# JL7016G8.net
KiCad netlist of a schematic drawn in Altium Designer
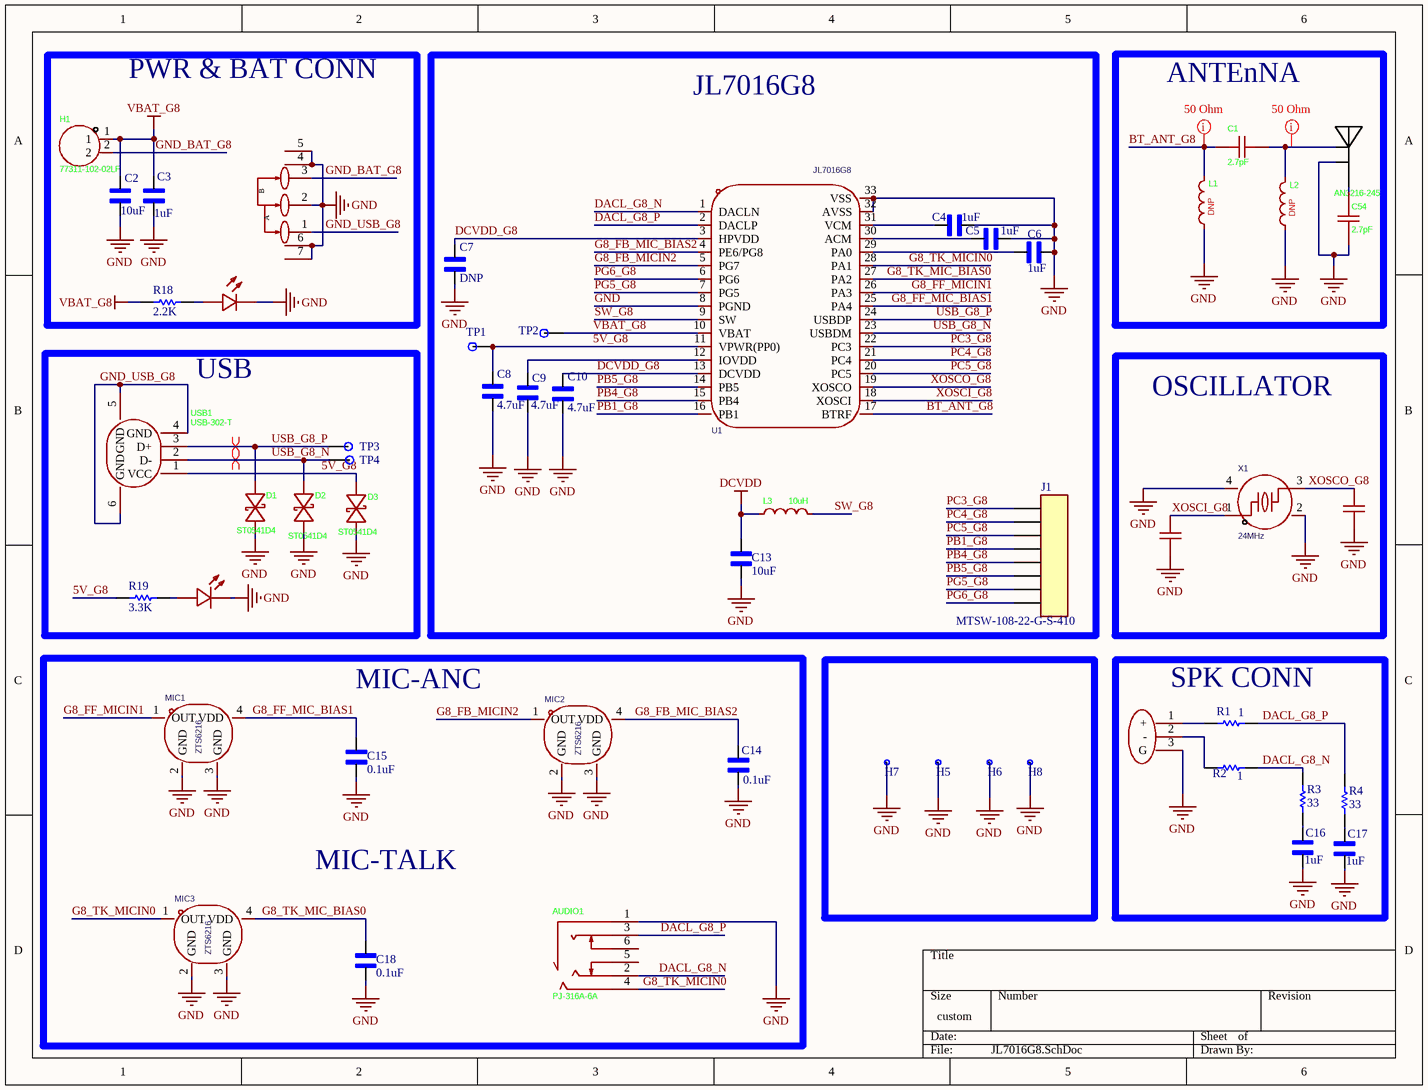
[diagram p0: JL7016G8.SchDoc]

(export (version "E")
  (design (tool "Eeschema 10.0.6"))
  (components
    (comp (ref "ANT1")
      (value "AN3216-245")
      (footprint "CUSTOME ANTEENA")
      (fields (field (name "MANUFACTURER") "Rainsun(霖昱微)") (field (name "POWER") "1W"))
      (libsource (lib "JEILI_DEV_BOARD") (part "AN3216-245"))
    )
    (comp (ref "AUDIO1")
      (value "PJ-316A-6A")
      (footprint "AUDIO-SMD_PJ-316A-6A")
      (fields (field (name "MANUFACTURER") "韩国韩荣"))
      (libsource (lib "JEILI_DEV_BOARD") (part "PJ-316A-6A"))
    )
    (comp (ref "C1")
      (value "2.7pF")
      (footprint "C0603")
      (fields (field (name "MANUFACTURER") "FH(风华)") (field (name "MANUFACTURER PART") "0603CG2R7C500NT"))
      (libsource (lib "JEILI_DEV_BOARD") (part "0603CG2R7C500NT"))
    )
    (comp (ref "C2")
      (value "10uF")
      (footprint "CAPC3216X170N")
      (libsource (lib "JEILI_DEV_BOARD") (part "CAP_10F"))
    )
    (comp (ref "C3")
      (value "1uF")
      (footprint "CAPC3216X170N")
      (libsource (lib "JEILI_DEV_BOARD") (part "CAP_1uF"))
    )
    (comp (ref "C4") (value "1uF") (footprint "CAPC3216X170N") (libsource (lib "") (part "CAP_1uF_2")))
    (comp (ref "C5") (value "1uF") (footprint "CAPC3216X170N") (libsource (lib "") (part "CAP_1uF_2")))
    (comp (ref "C6") (value "1uF") (footprint "CAPC3216X170N") (libsource (lib "") (part "CAP_1uF_2")))
    (comp (ref "C7")
      (value "DNP")
      (footprint "CAPC3216X170N")
      (fields (field (name "Comment") "1uF"))
      (libsource (lib "JEILI_DEV_BOARD") (part "CAP_1uF"))
    )
    (comp (ref "C8")
      (value "4.7uF")
      (footprint "CAPC3216X170N")
      (fields (field (name "Comment") "1uF"))
      (libsource (lib "JEILI_DEV_BOARD") (part "CAP_1uF"))
    )
    (comp (ref "C9")
      (value "4.7uF")
      (footprint "CAPC3216X170N")
      (fields (field (name "Comment") "1uF"))
      (libsource (lib "JEILI_DEV_BOARD") (part "CAP_1uF"))
    )
    (comp (ref "C10")
      (value "4.7uF")
      (footprint "CAPC3216X170N")
      (fields (field (name "Comment") "1uF"))
      (libsource (lib "JEILI_DEV_BOARD") (part "CAP_1uF"))
    )
    (comp (ref "C11")
      (value "12pF")
      (footprint "CAPC3216X170N")
      (fields
        (field (name "MANUFACTURER") "FH(风华)")
        (field (name "MANUFACTURER PART") "0402CG120J500NT")
        (field (name "TOLERANCE") "±5%")
      )
      (libsource (lib "JEILI_DEV_BOARD") (part "0402CG120J500NT"))
    )
    (comp (ref "C12")
      (value "12pF")
      (footprint "CAPC3216X170N")
      (fields
        (field (name "MANUFACTURER") "FH(风华)")
        (field (name "MANUFACTURER PART") "0402CG120J500NT")
        (field (name "TOLERANCE") "±5%")
      )
      (libsource (lib "JEILI_DEV_BOARD") (part "0402CG120J500NT"))
    )
    (comp (ref "C13")
      (value "10uF")
      (footprint "CAPC3216X170N")
      (libsource (lib "JEILI_DEV_BOARD") (part "CAP_10F"))
    )
    (comp (ref "C14")
      (value "0.1uF")
      (footprint "CAPC3216X170N")
      (description "100nF 10V X7R ±5% 0402 Multilayer Ceramic Capacitors MLCC - SMD/SMT ROHS")
      (fields (field (name "MANUFACTURER") "Walsin Tech Corp") (field (name "MFR.PART #") "0402B104J100CT"))
      (libsource (lib "Glasses_EEG_V2.0") (part "CAP_0.1uF"))
    )
    (comp (ref "C15")
      (value "0.1uF")
      (footprint "CAPC3216X170N")
      (description "100nF 10V X7R ±5% 0402 Multilayer Ceramic Capacitors MLCC - SMD/SMT ROHS")
      (fields (field (name "MANUFACTURER") "Walsin Tech Corp") (field (name "MFR.PART #") "0402B104J100CT"))
      (libsource (lib "Glasses_EEG_V2.0") (part "CAP_0.1uF"))
    )
    (comp (ref "C16") (value "1uF") (footprint "CAPC3216X170N") (libsource (lib "") (part "CAP_1uF_1")))
    (comp (ref "C17") (value "1uF") (footprint "CAPC3216X170N") (libsource (lib "") (part "CAP_1uF_1")))
    (comp (ref "C18")
      (value "0.1uF")
      (footprint "CAPC3216X170N")
      (description "100nF 10V X7R ±5% 0402 Multilayer Ceramic Capacitors MLCC - SMD/SMT ROHS")
      (fields (field (name "MANUFACTURER") "Walsin Tech Corp") (field (name "MFR.PART #") "0402B104J100CT"))
      (libsource (lib "Glasses_EEG_V2.0") (part "CAP_0.1uF"))
    )
    (comp (ref "C54")
      (value "2.7pF")
      (footprint "C0402")
      (fields (field (name "MANUFACTURER") "FH(风华)") (field (name "MANUFACTURER PART") "0603CG2R7C500NT"))
      (libsource (lib "JEILI_DEV_BOARD") (part "0603CG2R7C500NT"))
    )
    (comp (ref "D1")
      (value "ST0541D4")
      (footprint "DFN1006-BI")
      (fields (field (name "MANUFACTURER") "Leiditech(雷卯电子)"))
      (libsource (lib "JEILI_DEV_BOARD") (part "ST0541D4"))
    )
    (comp (ref "D2")
      (value "ST0541D4")
      (footprint "DFN1006-BI")
      (fields (field (name "MANUFACTURER") "Leiditech(雷卯电子)"))
      (libsource (lib "JEILI_DEV_BOARD") (part "ST0541D4"))
    )
    (comp (ref "D3")
      (value "ST0541D4")
      (footprint "DFN1006-BI")
      (fields (field (name "MANUFACTURER") "Leiditech(雷卯电子)"))
      (libsource (lib "JEILI_DEV_BOARD") (part "ST0541D4"))
    )
    (comp (ref "H1")
      (value "77311-102-02LF")
      (footprint "HDR-TH_2P-P2.54-V-M-1")
      (fields (field (name "MANUFACTURER") "Amphenol"))
      (libsource (lib "JEILI_DEV_BOARD") (part "77311-102-02LF"))
    )
    (comp (ref "H5") (value "MH") (footprint "MH") (libsource (lib "JEILI_DEV_BOARD") (part "MH")))
    (comp (ref "H6") (value "MH") (footprint "MH") (libsource (lib "JEILI_DEV_BOARD") (part "MH")))
    (comp (ref "H7") (value "MH") (footprint "MH") (libsource (lib "JEILI_DEV_BOARD") (part "MH")))
    (comp (ref "H8") (value "MH") (footprint "MH") (libsource (lib "JEILI_DEV_BOARD") (part "MH")))
    (comp (ref "J1")
      (value "MTSW-108-22-G-S-410")
      (footprint "SAMTEC_MTSW-108-22-G-S-410")
      (libsource (lib "JEILI_DEV_BOARD") (part "MTSW-108-22-G-S-410"))
    )
    (comp (ref "L1")
      (value "DNP")
      (footprint "L0603")
      (fields
        (field (name "MANUFACTURER") "muRata(村田)")
        (field (name "MANUFACTURER PART") "DFE18SAN1R0ME0L")
        (field (name "TOLERANCE") "±20%")
      )
      (libsource (lib "JEILI_DEV_BOARD") (part "33nH"))
    )
    (comp (ref "L2")
      (value "DNP")
      (footprint "L0603")
      (fields
        (field (name "MANUFACTURER") "muRata(村田)")
        (field (name "MANUFACTURER PART") "DFE18SAN1R0ME0L")
        (field (name "TOLERANCE") "±20%")
      )
      (libsource (lib "JEILI_DEV_BOARD") (part "33nH"))
    )
    (comp (ref "L3") (value "10uH") (footprint "L0603") (libsource (lib "JEILI_DEV_BOARD") (part "10uH")))
    (comp (ref "LED1")
      (value "LTST-C191GKT")
      (footprint "LED0603-R-RD_GREEN")
      (fields (field (name "MANUFACTURER") "LITEON(光宝)"))
      (libsource (lib "JEILI_DEV_BOARD") (part "LTST-C191GKT"))
    )
    (comp (ref "LED2")
      (value "KT-0603R")
      (footprint "LED0603-RD")
      (fields (field (name "MANUFACTURER") "KENTO"))
      (libsource (lib "JEILI_DEV_BOARD") (part "KT-0603R"))
    )
    (comp (ref "MIC1")
      (value "ZTS6216")
      (footprint "MIC-SMD_4P-L2.8-W1.9-P1.84-TL")
      (fields (field (name "MANUFACTURER") "ZILLTEK(钰太)"))
      (libsource (lib "Glasses_EEG_V2.0") (part "ZTS6216"))
    )
    (comp (ref "MIC2")
      (value "ZTS6216")
      (footprint "MIC-SMD_4P-L2.8-W1.9-P1.84-TL")
      (fields (field (name "MANUFACTURER") "ZILLTEK(钰太)"))
      (libsource (lib "Glasses_EEG_V2.0") (part "ZTS6216"))
    )
    (comp (ref "MIC3")
      (value "ZTS6216")
      (footprint "MIC-SMD_4P-L2.8-W1.9-P1.84-TL")
      (fields (field (name "MANUFACTURER") "ZILLTEK(钰太)"))
      (libsource (lib "Glasses_EEG_V2.0") (part "ZTS6216"))
    )
    (comp (ref "P1")
      (value "1.27-1*3P针")
      (footprint "HDR-TH_3P-P1.27-V-M-1")
      (fields (field (name "MANUFACTURER") "BOOMELE(博穆精密)"))
      (libsource (lib "JEILI_DEV_BOARD") (part "1.27-1*3P针"))
    )
    (comp (ref "R1")
      (value "1")
      (footprint "R0603")
      (fields
        (field (name "MANUFACTURER") "YAGEO")
        (field (name "MFR.PART #") "RC0402JR-0733RL")
        (field (name "JLCPCB PART #") "C137880")
      )
      (libsource (lib "JEILI_DEV_BOARD") (part "RES_1"))
    )
    (comp (ref "R2")
      (value "1")
      (footprint "R0603")
      (fields
        (field (name "MANUFACTURER") "YAGEO")
        (field (name "MFR.PART #") "RC0402JR-0733RL")
        (field (name "JLCPCB PART #") "C137880")
      )
      (libsource (lib "JEILI_DEV_BOARD") (part "RES_1"))
    )
    (comp (ref "R3")
      (value "33")
      (footprint "R0603")
      (fields
        (field (name "MANUFACTURER") "YAGEO")
        (field (name "MFR.PART #") "RC0402JR-0733RL")
        (field (name "JLCPCB PART #") "C137880")
      )
      (libsource (lib "JEILI_DEV_BOARD") (part "RES_33"))
    )
    (comp (ref "R4")
      (value "33")
      (footprint "R0603")
      (fields
        (field (name "MANUFACTURER") "YAGEO")
        (field (name "MFR.PART #") "RC0402JR-0733RL")
        (field (name "JLCPCB PART #") "C137880")
      )
      (libsource (lib "JEILI_DEV_BOARD") (part "RES_33"))
    )
    (comp (ref "R18")
      (value "2.2K")
      (footprint "R1206")
      (fields
        (field (name "MANUFACTURER") "YAGEO")
        (field (name "MFR.PART #") "RC0402JR-0733RL")
        (field (name "JLCPCB PART #") "C137880")
      )
      (libsource (lib "JEILI_DEV_BOARD") (part "RES_2.2K"))
    )
    (comp (ref "R19")
      (value "3.3K")
      (footprint "R1206")
      (fields
        (field (name "MANUFACTURER") "YAGEO")
        (field (name "MFR.PART #") "RC0402JR-0733RL")
        (field (name "JLCPCB PART #") "C137880")
      )
      (libsource (lib "JEILI_DEV_BOARD") (part "RES_3.3K"))
    )
    (comp (ref "SW1")
      (value "MK-12C02-G015")
      (footprint "SW-SMD_G-SWITCH_MK-12C02-G015")
      (fields (field (name "MANUFACTURER") "G-Switch(品赞)"))
      (libsource (lib "JEILI_DEV_BOARD") (part "MK-12C02-G015_C2911519"))
    )
    (comp (ref "TP1")
      (value "TP_1")
      (footprint "TP")
      (description "test point")
      (libsource (lib "JEILI_DEV_BOARD") (part "TP_1"))
    )
    (comp (ref "TP2")
      (value "TP_1")
      (footprint "TP")
      (description "test point")
      (libsource (lib "JEILI_DEV_BOARD") (part "TP_1"))
    )
    (comp (ref "TP3")
      (value "TP_1")
      (footprint "TP")
      (description "test point")
      (libsource (lib "JEILI_DEV_BOARD") (part "TP_1"))
    )
    (comp (ref "TP4")
      (value "TP_1")
      (footprint "TP")
      (description "test point")
      (libsource (lib "JEILI_DEV_BOARD") (part "TP_1"))
    )
    (comp (ref "U1")
      (value "JL7016G8")
      (footprint "QFN-32_L4.0-W4.0-P0.40-TL-EP2.7")
      (fields (field (name "MANUFACTURER") "JL(杰理)"))
      (libsource (lib "JEILI_DEV_BOARD") (part "JL7016G8"))
    )
    (comp (ref "USB1")
      (value "USB-302-T")
      (footprint "USB-A-TH_USB-302-T")
      (fields (field (name "MANUFACTURER") "SOFNG(硕方)"))
      (libsource (lib "JEILI_DEV_BOARD") (part "USB-302-T"))
    )
    (comp (ref "X1")
      (value "24MHz")
      (footprint "CRYSTAL-SMD_4P-L2.0-W1.6-BL-A")
      (fields
        (field (name "MANUFACTURER") "YXC(扬兴晶振)")
        (field (name "MANUFACTURER PART") "XL7EL89CKI-111YLC-24M")
      )
      (libsource (lib "Glasses_EEG_V2.0") (part "XL7EL89CKI-111YLC-24M"))
    )
  )
  (nets
    (net (code "1") (name "/5V_G8") (class "Default")
      (node (ref "C8") (pin "1") (pinfunction "1_1") (pintype "passive"))
      (node (ref "D3") (pin "2") (pinfunction "2_2") (pintype "passive"))
      (node (ref "R19") (pin "2") (pinfunction "2_2") (pintype "passive"))
      (node (ref "TP1") (pin "1") (pinfunction "1_1") (pintype "passive"))
      (node (ref "U1") (pin "11") (pinfunction "VPWR(PP0)_11") (pintype "passive"))
      (node (ref "USB1") (pin "1") (pinfunction "VCC_1") (pintype "passive"))
    )
    (net (code "2") (name "/BT_ANT_G8") (class "Default")
      (node (ref "C1") (pin "1") (pinfunction "1_1") (pintype "passive"))
      (node (ref "L1") (pin "2") (pinfunction "2_2") (pintype "passive"))
      (node (ref "U1") (pin "17") (pinfunction "BTRF_17") (pintype "passive"))
    )
    (net (code "3") (name "/DACL_G8_N") (class "Default")
      (node (ref "AUDIO1") (pin "2") (pinfunction "2_2") (pintype "passive"))
      (node (ref "R2") (pin "1") (pinfunction "1_1") (pintype "passive"))
      (node (ref "R3") (pin "1") (pinfunction "1_1") (pintype "passive"))
      (node (ref "U1") (pin "1") (pinfunction "DACLN_1") (pintype "passive"))
    )
    (net (code "4") (name "/DACL_G8_P") (class "Default")
      (node (ref "AUDIO1") (pin "3") (pinfunction "3_3") (pintype "passive"))
      (node (ref "R1") (pin "1") (pinfunction "1_1") (pintype "passive"))
      (node (ref "R4") (pin "1") (pinfunction "1_1") (pintype "passive"))
      (node (ref "U1") (pin "2") (pinfunction "DACLP_2") (pintype "passive"))
    )
    (net (code "5") (name "/DCVDD_G8") (class "Default")
      (node (ref "C10") (pin "1") (pinfunction "1_1") (pintype "passive"))
      (node (ref "C7") (pin "1") (pinfunction "1_1") (pintype "passive"))
      (node (ref "U1") (pin "13") (pinfunction "DCVDD_13") (pintype "passive"))
      (node (ref "U1") (pin "3") (pinfunction "HPVDD_3") (pintype "passive"))
    )
    (net (code "6") (name "/G8_FB_MICIN2") (class "Default")
      (node (ref "MIC2") (pin "1") (pinfunction "OUT_1") (pintype "passive"))
      (node (ref "U1") (pin "5") (pinfunction "PG7_5") (pintype "passive"))
    )
    (net (code "7") (name "/G8_FB_MIC_BIAS2") (class "Default")
      (node (ref "C14") (pin "2") (pinfunction "2_2") (pintype "passive"))
      (node (ref "MIC2") (pin "4") (pinfunction "VDD_4") (pintype "passive"))
      (node (ref "U1") (pin "4") (pinfunction "PE6/PG8_4") (pintype "passive"))
    )
    (net (code "8") (name "/G8_FF_MICIN1") (class "Default")
      (node (ref "MIC1") (pin "1") (pinfunction "OUT_1") (pintype "passive"))
      (node (ref "U1") (pin "26") (pinfunction "PA3_26") (pintype "passive"))
    )
    (net (code "9") (name "/G8_FF_MIC_BIAS1") (class "Default")
      (node (ref "C15") (pin "2") (pinfunction "2_2") (pintype "passive"))
      (node (ref "MIC1") (pin "4") (pinfunction "VDD_4") (pintype "passive"))
      (node (ref "U1") (pin "25") (pinfunction "PA4_25") (pintype "passive"))
    )
    (net (code "10") (name "/G8_TK_MICIN0") (class "Default")
      (node (ref "AUDIO1") (pin "4") (pinfunction "4_4") (pintype "passive"))
      (node (ref "MIC3") (pin "1") (pinfunction "OUT_1") (pintype "passive"))
      (node (ref "U1") (pin "28") (pinfunction "PA1_28") (pintype "passive"))
    )
    (net (code "11") (name "/G8_TK_MIC_BIAS0") (class "Default")
      (node (ref "C18") (pin "2") (pinfunction "2_2") (pintype "passive"))
      (node (ref "MIC3") (pin "4") (pinfunction "VDD_4") (pintype "passive"))
      (node (ref "U1") (pin "27") (pinfunction "PA2_27") (pintype "passive"))
    )
    (net (code "12") (name "/GND_BAT_G8") (class "Default")
      (node (ref "H1") (pin "2") (pinfunction "2_2") (pintype "passive"))
      (node (ref "SW1") (pin "3") (pinfunction "3_3") (pintype "passive"))
    )
    (net (code "13") (name "/GND_USB_G8") (class "Default")
      (node (ref "SW1") (pin "1") (pinfunction "1_1") (pintype "passive"))
      (node (ref "USB1") (pin "4") (pinfunction "GND_4") (pintype "passive"))
      (node (ref "USB1") (pin "5") (pinfunction "GND_5") (pintype "passive"))
      (node (ref "USB1") (pin "6") (pinfunction "GND_6") (pintype "passive"))
    )
    (net (code "14") (name "/PB1_G8") (class "Default")
      (node (ref "J1") (pin "04") (pinfunction "04_04") (pintype "passive"))
      (node (ref "U1") (pin "16") (pinfunction "PB1_16") (pintype "passive"))
    )
    (net (code "15") (name "/PB4_G8") (class "Default")
      (node (ref "J1") (pin "05") (pinfunction "05_05") (pintype "passive"))
      (node (ref "U1") (pin "15") (pinfunction "PB4_15") (pintype "passive"))
    )
    (net (code "16") (name "/PB5_G8") (class "Default")
      (node (ref "J1") (pin "06") (pinfunction "06_06") (pintype "passive"))
      (node (ref "U1") (pin "14") (pinfunction "PB5_14") (pintype "passive"))
    )
    (net (code "17") (name "/PC3_G8") (class "Default")
      (node (ref "J1") (pin "01") (pinfunction "01_01") (pintype "passive"))
      (node (ref "U1") (pin "22") (pinfunction "PC3_22") (pintype "passive"))
    )
    (net (code "18") (name "/PC4_G8") (class "Default")
      (node (ref "J1") (pin "02") (pinfunction "02_02") (pintype "passive"))
      (node (ref "U1") (pin "21") (pinfunction "PC4_21") (pintype "passive"))
    )
    (net (code "19") (name "/PC5_G8") (class "Default")
      (node (ref "J1") (pin "03") (pinfunction "03_03") (pintype "passive"))
      (node (ref "U1") (pin "20") (pinfunction "PC5_20") (pintype "passive"))
    )
    (net (code "20") (name "/PG5_G8") (class "Default")
      (node (ref "J1") (pin "07") (pinfunction "07_07") (pintype "passive"))
      (node (ref "U1") (pin "7") (pinfunction "PG5_7") (pintype "passive"))
    )
    (net (code "21") (name "/PG6_G8") (class "Default")
      (node (ref "J1") (pin "08") (pinfunction "08_08") (pintype "passive"))
      (node (ref "U1") (pin "6") (pinfunction "PG6_6") (pintype "passive"))
    )
    (net (code "22") (name "/SW_G8") (class "Default")
      (node (ref "L3") (pin "2") (pinfunction "2_2") (pintype "passive"))
      (node (ref "U1") (pin "9") (pinfunction "SW_9") (pintype "passive"))
    )
    (net (code "23") (name "/USB_G8_N") (class "Default")
      (node (ref "D2") (pin "2") (pinfunction "2_2") (pintype "passive"))
      (node (ref "TP4") (pin "1") (pinfunction "1_1") (pintype "passive"))
      (node (ref "U1") (pin "23") (pinfunction "USBDM_23") (pintype "passive"))
      (node (ref "USB1") (pin "2") (pinfunction "D-_2") (pintype "passive"))
    )
    (net (code "24") (name "/USB_G8_P") (class "Default")
      (node (ref "D1") (pin "2") (pinfunction "2_2") (pintype "passive"))
      (node (ref "TP3") (pin "1") (pinfunction "1_1") (pintype "passive"))
      (node (ref "U1") (pin "24") (pinfunction "USBDP_24") (pintype "passive"))
      (node (ref "USB1") (pin "3") (pinfunction "D+_3") (pintype "passive"))
    )
    (net (code "25") (name "/XOSCI_G8") (class "Default")
      (node (ref "C12") (pin "2") (pinfunction "2_2") (pintype "passive"))
      (node (ref "U1") (pin "18") (pinfunction "XOSCI_18") (pintype "passive"))
      (node (ref "X1") (pin "1") (pinfunction "1_1") (pintype "passive"))
    )
    (net (code "26") (name "/XOSCO_G8") (class "Default")
      (node (ref "C11") (pin "2") (pinfunction "2_2") (pintype "passive"))
      (node (ref "U1") (pin "19") (pinfunction "XOSCO_19") (pintype "passive"))
      (node (ref "X1") (pin "3") (pinfunction "3_3") (pintype "passive"))
    )
    (net (code "27") (name "DCVDD") (class "Default")
      (node (ref "C13") (pin "2") (pinfunction "2_2") (pintype "passive"))
      (node (ref "L3") (pin "1") (pinfunction "1_1") (pintype "passive"))
    )
    (net (code "28") (name "GND") (class "Default")
      (node (ref "ANT1") (pin "2") (pinfunction "2_2") (pintype "passive"))
      (node (ref "AUDIO1") (pin "1") (pinfunction "1_1") (pintype "passive"))
      (node (ref "C10") (pin "2") (pinfunction "2_2") (pintype "passive"))
      (node (ref "C11") (pin "1") (pinfunction "1_1") (pintype "passive"))
      (node (ref "C12") (pin "1") (pinfunction "1_1") (pintype "passive"))
      (node (ref "C13") (pin "1") (pinfunction "1_1") (pintype "passive"))
      (node (ref "C14") (pin "1") (pinfunction "1_1") (pintype "passive"))
      (node (ref "C15") (pin "1") (pinfunction "1_1") (pintype "passive"))
      (node (ref "C16") (pin "1") (pinfunction "1_1") (pintype "passive"))
      (node (ref "C17") (pin "1") (pinfunction "1_1") (pintype "passive"))
      (node (ref "C18") (pin "1") (pinfunction "1_1") (pintype "passive"))
      (node (ref "C2") (pin "1") (pinfunction "1_1") (pintype "passive"))
      (node (ref "C3") (pin "2") (pinfunction "2_2") (pintype "passive"))
      (node (ref "C4") (pin "2") (pinfunction "2_2") (pintype "passive"))
      (node (ref "C5") (pin "2") (pinfunction "2_2") (pintype "passive"))
      (node (ref "C54") (pin "1") (pinfunction "1_1") (pintype "passive"))
      (node (ref "C6") (pin "2") (pinfunction "2_2") (pintype "passive"))
      (node (ref "C7") (pin "2") (pinfunction "2_2") (pintype "passive"))
      (node (ref "C8") (pin "2") (pinfunction "2_2") (pintype "passive"))
      (node (ref "C9") (pin "2") (pinfunction "2_2") (pintype "passive"))
      (node (ref "D1") (pin "1") (pinfunction "1_1") (pintype "passive"))
      (node (ref "D2") (pin "1") (pinfunction "1_1") (pintype "passive"))
      (node (ref "D3") (pin "1") (pinfunction "1_1") (pintype "passive"))
      (node (ref "H5") (pin "1") (pinfunction "1_1") (pintype "passive"))
      (node (ref "H6") (pin "1") (pinfunction "1_1") (pintype "passive"))
      (node (ref "H7") (pin "1") (pinfunction "1_1") (pintype "passive"))
      (node (ref "H8") (pin "1") (pinfunction "1_1") (pintype "passive"))
      (node (ref "L1") (pin "1") (pinfunction "1_1") (pintype "passive"))
      (node (ref "L2") (pin "1") (pinfunction "1_1") (pintype "passive"))
      (node (ref "LED1") (pin "2") (pinfunction "C_2") (pintype "passive"))
      (node (ref "LED2") (pin "1") (pinfunction "K_1") (pintype "passive"))
      (node (ref "MIC1") (pin "2") (pinfunction "GND_2") (pintype "passive"))
      (node (ref "MIC1") (pin "3") (pinfunction "GND_3") (pintype "passive"))
      (node (ref "MIC2") (pin "2") (pinfunction "GND_2") (pintype "passive"))
      (node (ref "MIC2") (pin "3") (pinfunction "GND_3") (pintype "passive"))
      (node (ref "MIC3") (pin "2") (pinfunction "GND_2") (pintype "passive"))
      (node (ref "MIC3") (pin "3") (pinfunction "GND_3") (pintype "passive"))
      (node (ref "P1") (pin "3") (pinfunction "G_3") (pintype "passive"))
      (node (ref "SW1") (pin "2") (pinfunction "2_2") (pintype "passive"))
      (node (ref "SW1") (pin "4") (pinfunction "4_4") (pintype "passive"))
      (node (ref "SW1") (pin "5") (pinfunction "5_5") (pintype "passive"))
      (node (ref "SW1") (pin "6") (pinfunction "6_6") (pintype "passive"))
      (node (ref "SW1") (pin "7") (pinfunction "7_7") (pintype "passive"))
      (node (ref "U1") (pin "32") (pinfunction "AVSS_32") (pintype "passive"))
      (node (ref "U1") (pin "33") (pinfunction "VSS_33") (pintype "passive"))
      (node (ref "U1") (pin "8") (pinfunction "PGND_8") (pintype "passive"))
      (node (ref "X1") (pin "2") (pinfunction "GND_2") (pintype "passive"))
      (node (ref "X1") (pin "4") (pinfunction "GND_4") (pintype "passive"))
    )
    (net (code "29") (name "Net-(ANT1-Pad1)") (class "Default")
      (node (ref "ANT1") (pin "1") (pinfunction "1_1") (pintype "passive"))
      (node (ref "C1") (pin "2") (pinfunction "2_2") (pintype "passive"))
      (node (ref "L2") (pin "2") (pinfunction "2_2") (pintype "passive"))
    )
    (net (code "30") (name "Net-(ANT1-Pad3)") (class "Default")
      (node (ref "ANT1") (pin "3") (pinfunction "3_3") (pintype "passive"))
      (node (ref "C54") (pin "2") (pinfunction "2_2") (pintype "passive"))
    )
    (net (code "31") (name "Net-(C16-Pad2)") (class "Default")
      (node (ref "C16") (pin "2") (pinfunction "2_2") (pintype "passive"))
      (node (ref "R3") (pin "2") (pinfunction "2_2") (pintype "passive"))
    )
    (net (code "32") (name "Net-(C17-Pad2)") (class "Default")
      (node (ref "C17") (pin "2") (pinfunction "2_2") (pintype "passive"))
      (node (ref "R4") (pin "2") (pinfunction "2_2") (pintype "passive"))
    )
    (net (code "33") (name "Net-(LED1-A)") (class "Default")
      (node (ref "LED1") (pin "1") (pinfunction "A_1") (pintype "passive"))
      (node (ref "R18") (pin "1") (pinfunction "1_1") (pintype "passive"))
    )
    (net (code "34") (name "Net-(LED2-A)") (class "Default")
      (node (ref "LED2") (pin "2") (pinfunction "A_2") (pintype "passive"))
      (node (ref "R19") (pin "1") (pinfunction "1_1") (pintype "passive"))
    )
    (net (code "35") (name "Net-(P1-+)") (class "Default")
      (node (ref "P1") (pin "1") (pinfunction "+_1") (pintype "passive"))
      (node (ref "R1") (pin "2") (pinfunction "2_2") (pintype "passive"))
    )
    (net (code "36") (name "Net-(P1--)") (class "Default")
      (node (ref "P1") (pin "2") (pinfunction "-_2") (pintype "passive"))
      (node (ref "R2") (pin "2") (pinfunction "2_2") (pintype "passive"))
    )
    (net (code "37") (name "Net-(U1-ACM)") (class "Default")
      (node (ref "C5") (pin "1") (pinfunction "1_1") (pintype "passive"))
      (node (ref "U1") (pin "30") (pinfunction "ACM_30") (pintype "passive"))
    )
    (net (code "38") (name "Net-(U1-IOVDD)") (class "Default")
      (node (ref "C9") (pin "1") (pinfunction "1_1") (pintype "passive"))
      (node (ref "U1") (pin "12") (pinfunction "IOVDD_12") (pintype "passive"))
    )
    (net (code "39") (name "Net-(U1-PA0)") (class "Default")
      (node (ref "C6") (pin "1") (pinfunction "1_1") (pintype "passive"))
      (node (ref "U1") (pin "29") (pinfunction "PA0_29") (pintype "passive"))
    )
    (net (code "40") (name "Net-(U1-VCM)") (class "Default")
      (node (ref "C4") (pin "1") (pinfunction "1_1") (pintype "passive"))
      (node (ref "U1") (pin "31") (pinfunction "VCM_31") (pintype "passive"))
    )
    (net (code "41") (name "VBAT_G8") (class "Default")
      (node (ref "C2") (pin "2") (pinfunction "2_2") (pintype "passive"))
      (node (ref "C3") (pin "1") (pinfunction "1_1") (pintype "passive"))
      (node (ref "H1") (pin "1") (pinfunction "1_1") (pintype "passive"))
      (node (ref "R18") (pin "2") (pinfunction "2_2") (pintype "passive"))
      (node (ref "TP2") (pin "1") (pinfunction "1_1") (pintype "passive"))
      (node (ref "U1") (pin "10") (pinfunction "VBAT_10") (pintype "passive"))
    )
    (net (code "42") (name "unconnected-(AUDIO1-Pad5)") (class "Default")
      (node (ref "AUDIO1") (pin "5") (pinfunction "5_5") (pintype "passive"))
    )
    (net (code "43") (name "unconnected-(AUDIO1-Pad6)") (class "Default")
      (node (ref "AUDIO1") (pin "6") (pinfunction "6_6") (pintype "passive"))
    )
  )
)
